# Danger_Shield-v17.net
KiCad netlist of a schematic drawn in EAGLE
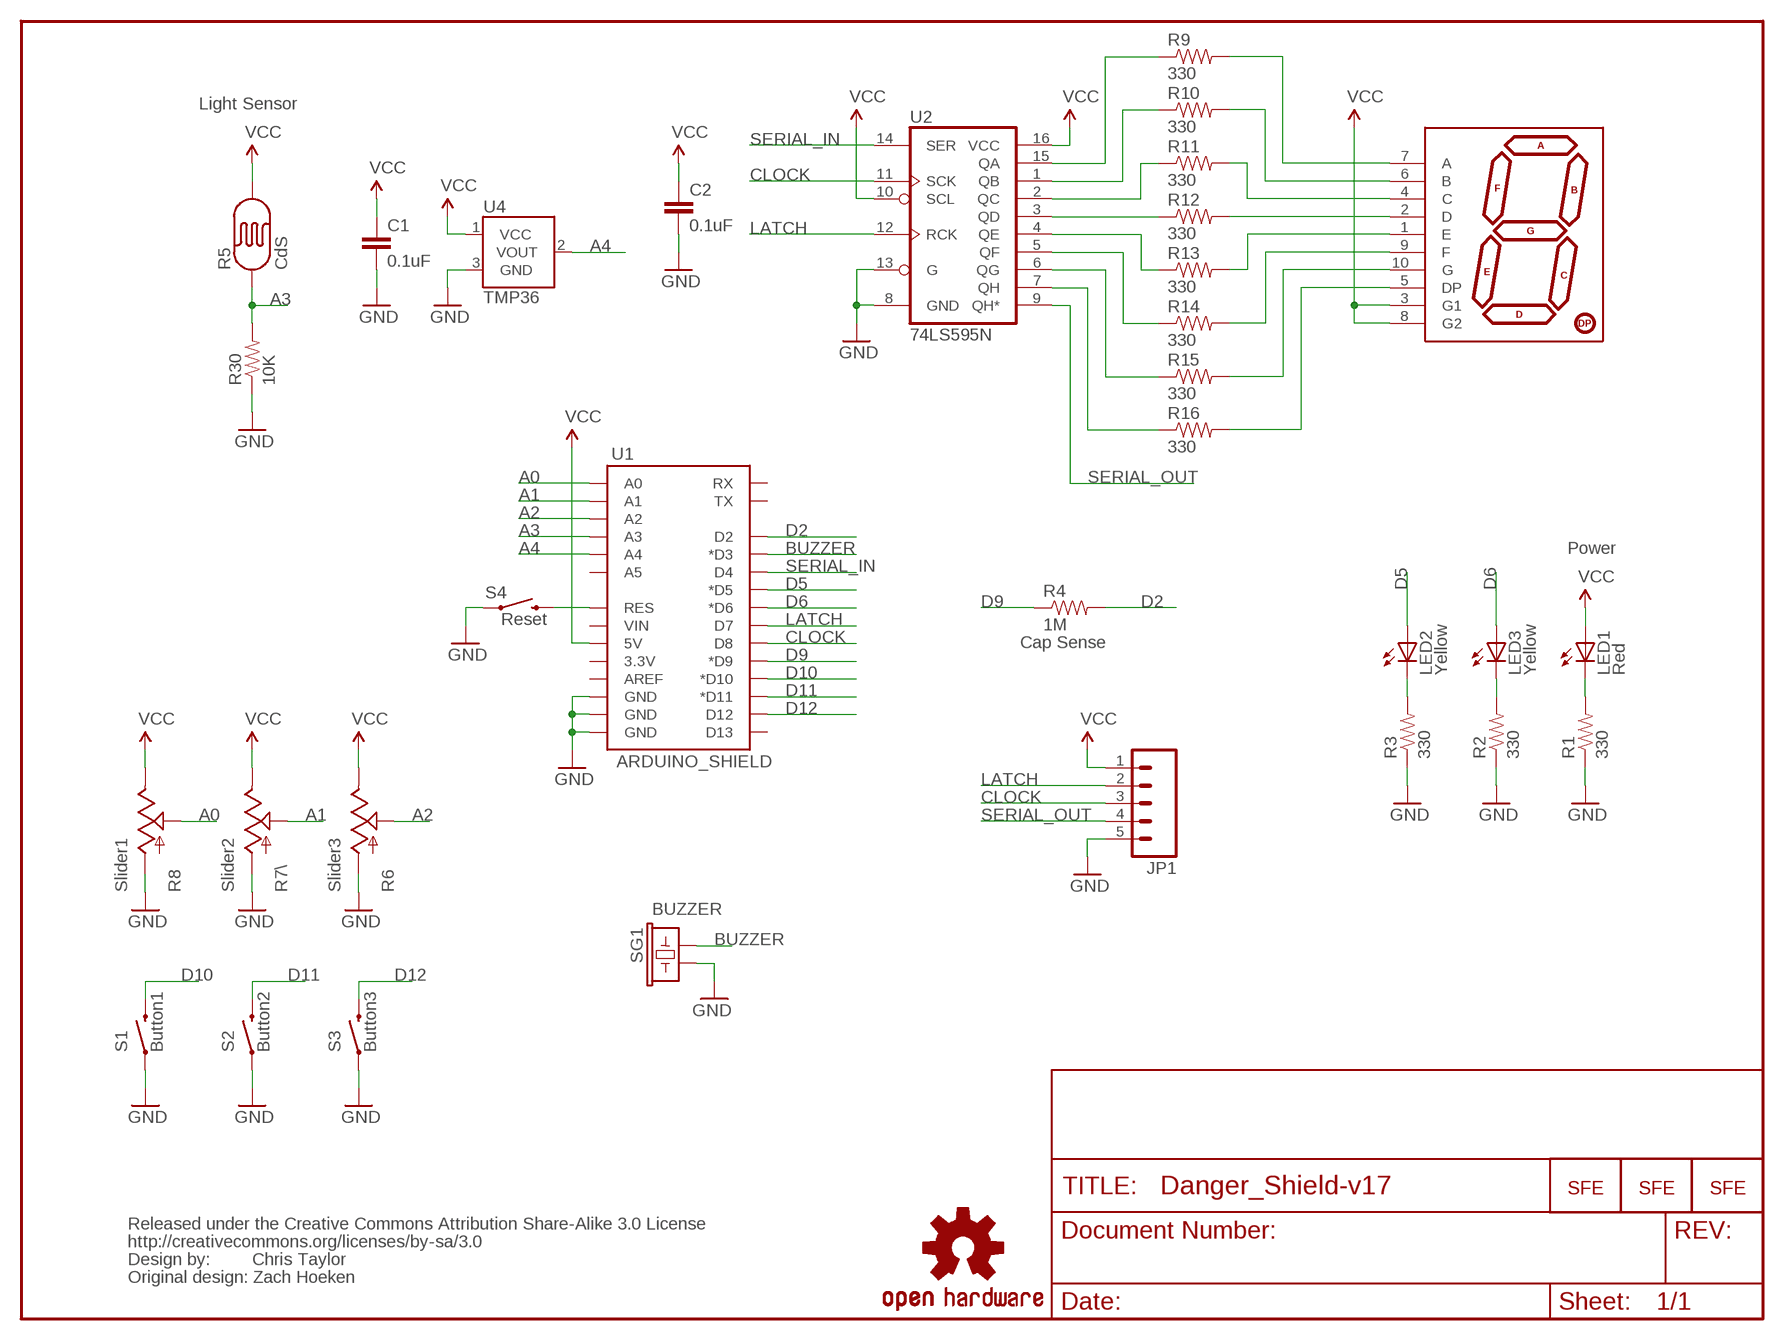
[diagram p0: schematic, sheet 1]

(export (version "E")
  (design (tool "Eeschema 10.0.6"))
  (components
    (comp (ref "C1")
      (value "0.1uF")
      (footprint "eagle-import:CAP-PTH-SMALL2")
      (libsource (lib "eagle-import") (part "CAPPTH2"))
    )
    (comp (ref "C2")
      (value "0.1uF")
      (footprint "eagle-import:CAP-PTH-SMALL2")
      (libsource (lib "eagle-import") (part "CAPPTH2"))
    )
    (comp (ref "JP1")
      (value "M05PTH")
      (footprint "eagle-import:1X05")
      (libsource (lib "eagle-import") (part "M05PTH"))
    )
    (comp (ref "JP2")
      (value "LOGO-SFENEW")
      (footprint "eagle-import:SFE-NEW-WEBLOGO")
      (libsource (lib "eagle-import") (part "LOGO-SFENEW"))
    )
    (comp (ref "JP3")
      (value "LOGO-SFENEW")
      (footprint "eagle-import:SFE-NEW-WEBLOGO")
      (libsource (lib "eagle-import") (part "LOGO-SFENEW"))
    )
    (comp (ref "JP5")
      (value "LOGO-SFESK")
      (footprint "eagle-import:SFE-LOGO-FLAME")
      (libsource (lib "eagle-import") (part "LOGO-SFESK"))
    )
    (comp (ref "LED1")
      (value "Red")
      (footprint "eagle-import:LED5MM")
      (libsource (lib "eagle-import") (part "LED5MM"))
    )
    (comp (ref "LED2")
      (value "Yellow")
      (footprint "eagle-import:LED5MM")
      (libsource (lib "eagle-import") (part "LED5MM"))
    )
    (comp (ref "LED3")
      (value "Yellow")
      (footprint "eagle-import:LED5MM")
      (libsource (lib "eagle-import") (part "LED5MM"))
    )
    (comp (ref "R1")
      (value "330")
      (footprint "eagle-import:AXIAL-0.3")
      (libsource (lib "eagle-import") (part "RESISTORAXIAL-0.3"))
    )
    (comp (ref "R2")
      (value "330")
      (footprint "eagle-import:AXIAL-0.3")
      (libsource (lib "eagle-import") (part "RESISTORAXIAL-0.3"))
    )
    (comp (ref "R3")
      (value "330")
      (footprint "eagle-import:AXIAL-0.3")
      (libsource (lib "eagle-import") (part "RESISTORAXIAL-0.3"))
    )
    (comp (ref "R4")
      (value "1M")
      (footprint "eagle-import:AXIAL-0.3")
      (libsource (lib "eagle-import") (part "RESISTORAXIAL-0.3"))
    )
    (comp (ref "R5")
      (value "CdS")
      (footprint "eagle-import:PHOTOCELL")
      (libsource (lib "eagle-import") (part "PHOTOCELLPTH"))
    )
    (comp (ref "R6")
      (value "Slider3")
      (footprint "eagle-import:SLIDER")
      (libsource (lib "eagle-import") (part "SLIDER"))
    )
    (comp (ref "R7\\")
      (value "Slider2")
      (footprint "eagle-import:SLIDER")
      (libsource (lib "eagle-import") (part "SLIDER"))
    )
    (comp (ref "R8")
      (value "Slider1")
      (footprint "eagle-import:SLIDER")
      (libsource (lib "eagle-import") (part "SLIDER"))
    )
    (comp (ref "R9")
      (value "330")
      (footprint "eagle-import:AXIAL-0.3")
      (libsource (lib "eagle-import") (part "RESISTORAXIAL-0.3"))
    )
    (comp (ref "R10")
      (value "330")
      (footprint "eagle-import:AXIAL-0.3")
      (libsource (lib "eagle-import") (part "RESISTORAXIAL-0.3"))
    )
    (comp (ref "R11")
      (value "330")
      (footprint "eagle-import:AXIAL-0.3")
      (libsource (lib "eagle-import") (part "RESISTORAXIAL-0.3"))
    )
    (comp (ref "R12")
      (value "330")
      (footprint "eagle-import:AXIAL-0.3")
      (libsource (lib "eagle-import") (part "RESISTORAXIAL-0.3"))
    )
    (comp (ref "R13")
      (value "330")
      (footprint "eagle-import:AXIAL-0.3")
      (libsource (lib "eagle-import") (part "RESISTORAXIAL-0.3"))
    )
    (comp (ref "R14")
      (value "330")
      (footprint "eagle-import:AXIAL-0.3")
      (libsource (lib "eagle-import") (part "RESISTORAXIAL-0.3"))
    )
    (comp (ref "R15")
      (value "330")
      (footprint "eagle-import:AXIAL-0.3")
      (libsource (lib "eagle-import") (part "RESISTORAXIAL-0.3"))
    )
    (comp (ref "R16")
      (value "330")
      (footprint "eagle-import:AXIAL-0.3")
      (libsource (lib "eagle-import") (part "RESISTORAXIAL-0.3"))
    )
    (comp (ref "R30")
      (value "10K")
      (footprint "eagle-import:AXIAL-0.3")
      (libsource (lib "eagle-import") (part "RESISTORAXIAL-0.3"))
    )
    (comp (ref "S1")
      (value "Button1")
      (footprint "eagle-import:TACTILE-PTH-12MM")
      (libsource (lib "eagle-import") (part "SWITCH-MOMENTARY-212MM"))
    )
    (comp (ref "S2")
      (value "Button2")
      (footprint "eagle-import:TACTILE-PTH-12MM")
      (libsource (lib "eagle-import") (part "SWITCH-MOMENTARY-212MM"))
    )
    (comp (ref "S3")
      (value "Button3")
      (footprint "eagle-import:TACTILE-PTH-12MM")
      (libsource (lib "eagle-import") (part "SWITCH-MOMENTARY-212MM"))
    )
    (comp (ref "S4")
      (value "Reset")
      (footprint "eagle-import:TACTILE-PTH")
      (libsource (lib "eagle-import") (part "SWITCH-MOMENTARY-2PTH"))
    )
    (comp (ref "SG1")
      (value "BUZZER")
      (footprint "eagle-import:BUZZER-12MM")
      (libsource (lib "eagle-import") (part "BUZZERPTH"))
    )
    (comp (ref "U$1")
      (value "CREATIVE_COMMONS")
      (footprint "eagle-import:CREATIVE_COMMONS")
      (libsource (lib "eagle-import") (part "CREATIVE_COMMONS"))
    )
    (comp (ref "U$2")
      (value "OSHW-LOGOM")
      (footprint "eagle-import:OSHW-LOGO-M")
      (libsource (lib "eagle-import") (part "OSHW-LOGOM"))
    )
    (comp (ref "U$6")
      (value "7-SEGMENT-DISPLAY-1\"-RED")
      (footprint "eagle-import:7-SEGMENT-1_PTH")
      (libsource (lib "eagle-import") (part "7-SEGMENT-DISPLAY-1{dblquote}-RED"))
    )
    (comp (ref "U1")
      (value "ARDUINO_SHIELD")
      (footprint "eagle-import:DUEMILANOVE_VIAS")
      (libsource (lib "eagle-import") (part "ARDUINO_SHIELDNO_SILK"))
    )
    (comp (ref "U2")
      (value "74LS595N")
      (footprint "eagle-import:DIL16")
      (libsource (lib "eagle-import") (part "74595NLS"))
    )
    (comp (ref "U4")
      (value "TMP36")
      (footprint "eagle-import:TO-92")
      (libsource (lib "eagle-import") (part "TMP36GT9"))
    )
  )
  (nets
    (net (code "1") (name "/A0") (class "Default")
      (node (ref "R8") (pin "2A") (pinfunction "S_2A") (pintype "passive"))
      (node (ref "U1") (pin "A0") (pinfunction "A0_A0") (pintype "bidirectional"))
    )
    (net (code "2") (name "/A1") (class "Default")
      (node (ref "R7\\") (pin "2A") (pinfunction "S_2A") (pintype "passive"))
      (node (ref "U1") (pin "A1") (pinfunction "A1_A1") (pintype "bidirectional"))
    )
    (net (code "3") (name "/A2") (class "Default")
      (node (ref "R6") (pin "2A") (pinfunction "S_2A") (pintype "passive"))
      (node (ref "U1") (pin "A2") (pinfunction "A2_A2") (pintype "bidirectional"))
    )
    (net (code "4") (name "/A3") (class "Default")
      (node (ref "R30") (pin "P$2") (pinfunction "2_P$2") (pintype "passive"))
      (node (ref "R5") (pin "1") (pinfunction "P$1_1") (pintype "bidirectional"))
      (node (ref "U1") (pin "A3") (pinfunction "A3_A3") (pintype "bidirectional"))
    )
    (net (code "5") (name "/A4") (class "Default")
      (node (ref "U1") (pin "A4") (pinfunction "A4_A4") (pintype "bidirectional"))
      (node (ref "U4") (pin "2") (pinfunction "VOUT_2") (pintype "bidirectional"))
    )
    (net (code "6") (name "/BUZZER") (class "Default")
      (node (ref "SG1") (pin "+") (pinfunction "1_+") (pintype "passive"))
      (node (ref "U1") (pin "D3") (pinfunction "*D3_D3") (pintype "bidirectional"))
    )
    (net (code "7") (name "/CLOCK") (class "Default")
      (node (ref "JP1") (pin "3") (pinfunction "3_3") (pintype "passive"))
      (node (ref "U1") (pin "D8") (pinfunction "D8_D8") (pintype "bidirectional"))
      (node (ref "U2") (pin "11") (pinfunction "SCK_11") (pintype "input"))
    )
    (net (code "8") (name "/D2") (class "Default")
      (node (ref "R4") (pin "P$2") (pinfunction "2_P$2") (pintype "passive"))
      (node (ref "U1") (pin "D2") (pinfunction "D2_D2") (pintype "bidirectional"))
    )
    (net (code "9") (name "/D5") (class "Default")
      (node (ref "LED2") (pin "A") (pinfunction "A_A") (pintype "passive"))
      (node (ref "U1") (pin "D5") (pinfunction "*D5_D5") (pintype "bidirectional"))
    )
    (net (code "10") (name "/D6") (class "Default")
      (node (ref "LED3") (pin "A") (pinfunction "A_A") (pintype "passive"))
      (node (ref "U1") (pin "D6") (pinfunction "*D6_D6") (pintype "bidirectional"))
    )
    (net (code "11") (name "/D9") (class "Default")
      (node (ref "R4") (pin "P$1") (pinfunction "1_P$1") (pintype "passive"))
      (node (ref "U1") (pin "D9") (pinfunction "*D9_D9") (pintype "bidirectional"))
    )
    (net (code "12") (name "/D10") (class "Default")
      (node (ref "S1") (pin "3") (pinfunction "2_3") (pintype "passive"))
      (node (ref "U1") (pin "D10") (pinfunction "*D10_D10") (pintype "bidirectional"))
    )
    (net (code "13") (name "/D11") (class "Default")
      (node (ref "S2") (pin "3") (pinfunction "2_3") (pintype "passive"))
      (node (ref "U1") (pin "D11") (pinfunction "*D11_D11") (pintype "bidirectional"))
    )
    (net (code "14") (name "/D12") (class "Default")
      (node (ref "S3") (pin "3") (pinfunction "2_3") (pintype "passive"))
      (node (ref "U1") (pin "D12") (pinfunction "D12_D12") (pintype "bidirectional"))
    )
    (net (code "15") (name "/LATCH") (class "Default")
      (node (ref "JP1") (pin "2") (pinfunction "2_2") (pintype "passive"))
      (node (ref "U1") (pin "D7") (pinfunction "D7_D7") (pintype "bidirectional"))
      (node (ref "U2") (pin "12") (pinfunction "RCK_12") (pintype "input"))
    )
    (net (code "16") (name "/SERIAL_IN") (class "Default")
      (node (ref "U1") (pin "D4") (pinfunction "D4_D4") (pintype "bidirectional"))
      (node (ref "U2") (pin "14") (pinfunction "SER_14") (pintype "input"))
    )
    (net (code "17") (name "/SERIAL_OUT") (class "Default")
      (node (ref "JP1") (pin "4") (pinfunction "4_4") (pintype "passive"))
      (node (ref "U2") (pin "9") (pinfunction "QH*_9") (pintype "tri_state"))
    )
    (net (code "18") (name "GND") (class "Default")
      (node (ref "C1") (pin "2") (pinfunction "2_2") (pintype "passive"))
      (node (ref "C2") (pin "2") (pinfunction "2_2") (pintype "passive"))
      (node (ref "JP1") (pin "5") (pinfunction "5_5") (pintype "passive"))
      (node (ref "R1") (pin "P$1") (pinfunction "1_P$1") (pintype "passive"))
      (node (ref "R2") (pin "P$1") (pinfunction "1_P$1") (pintype "passive"))
      (node (ref "R3") (pin "P$1") (pinfunction "1_P$1") (pintype "passive"))
      (node (ref "R30") (pin "P$1") (pinfunction "1_P$1") (pintype "passive"))
      (node (ref "R6") (pin "3") (pinfunction "A_3") (pintype "passive"))
      (node (ref "R7\\") (pin "3") (pinfunction "A_3") (pintype "passive"))
      (node (ref "R8") (pin "3") (pinfunction "A_3") (pintype "passive"))
      (node (ref "S1") (pin "1") (pinfunction "1_1") (pintype "passive"))
      (node (ref "S2") (pin "1") (pinfunction "1_1") (pintype "passive"))
      (node (ref "S3") (pin "1") (pinfunction "1_1") (pintype "passive"))
      (node (ref "S4") (pin "1") (pinfunction "1_1") (pintype "passive"))
      (node (ref "SG1") (pin "-") (pinfunction "2_-") (pintype "passive"))
      (node (ref "U1") (pin "GND@0") (pinfunction "GND_GND@0") (pintype "bidirectional"))
      (node (ref "U1") (pin "GND@1") (pinfunction "GND_GND@1") (pintype "bidirectional"))
      (node (ref "U1") (pin "GND@2") (pinfunction "GND_GND@2") (pintype "bidirectional"))
      (node (ref "U2") (pin "13") (pinfunction "G_13") (pintype "input"))
      (node (ref "U2") (pin "8") (pinfunction "GND_8") (pintype "power_in"))
      (node (ref "U4") (pin "3") (pinfunction "GND_3") (pintype "bidirectional"))
    )
    (net (code "19") (name "Net-(LED1-C)") (class "Default")
      (node (ref "LED1") (pin "K") (pinfunction "C_K") (pintype "passive"))
      (node (ref "R1") (pin "P$2") (pinfunction "2_P$2") (pintype "passive"))
    )
    (net (code "20") (name "Net-(LED2-C)") (class "Default")
      (node (ref "LED2") (pin "K") (pinfunction "C_K") (pintype "passive"))
      (node (ref "R3") (pin "P$2") (pinfunction "2_P$2") (pintype "passive"))
    )
    (net (code "21") (name "Net-(LED3-C)") (class "Default")
      (node (ref "LED3") (pin "K") (pinfunction "C_K") (pintype "passive"))
      (node (ref "R2") (pin "P$2") (pinfunction "2_P$2") (pintype "passive"))
    )
    (net (code "22") (name "Net-(R9-1)") (class "Default")
      (node (ref "R9") (pin "P$1") (pinfunction "1_P$1") (pintype "passive"))
      (node (ref "U2") (pin "15") (pinfunction "QA_15") (pintype "tri_state"))
    )
    (net (code "23") (name "Net-(R9-2)") (class "Default")
      (node (ref "R9") (pin "P$2") (pinfunction "2_P$2") (pintype "passive"))
      (node (ref "U$6") (pin "7") (pinfunction "A_7") (pintype "bidirectional"))
    )
    (net (code "24") (name "Net-(R10-1)") (class "Default")
      (node (ref "R10") (pin "P$1") (pinfunction "1_P$1") (pintype "passive"))
      (node (ref "U2") (pin "1") (pinfunction "QB_1") (pintype "tri_state"))
    )
    (net (code "25") (name "Net-(R10-2)") (class "Default")
      (node (ref "R10") (pin "P$2") (pinfunction "2_P$2") (pintype "passive"))
      (node (ref "U$6") (pin "6") (pinfunction "B_6") (pintype "bidirectional"))
    )
    (net (code "26") (name "Net-(R11-1)") (class "Default")
      (node (ref "R11") (pin "P$1") (pinfunction "1_P$1") (pintype "passive"))
      (node (ref "U2") (pin "2") (pinfunction "QC_2") (pintype "tri_state"))
    )
    (net (code "27") (name "Net-(R11-2)") (class "Default")
      (node (ref "R11") (pin "P$2") (pinfunction "2_P$2") (pintype "passive"))
      (node (ref "U$6") (pin "4") (pinfunction "C_4") (pintype "bidirectional"))
    )
    (net (code "28") (name "Net-(R12-1)") (class "Default")
      (node (ref "R12") (pin "P$1") (pinfunction "1_P$1") (pintype "passive"))
      (node (ref "U2") (pin "3") (pinfunction "QD_3") (pintype "tri_state"))
    )
    (net (code "29") (name "Net-(R12-2)") (class "Default")
      (node (ref "R12") (pin "P$2") (pinfunction "2_P$2") (pintype "passive"))
      (node (ref "U$6") (pin "2") (pinfunction "D_2") (pintype "bidirectional"))
    )
    (net (code "30") (name "Net-(R13-1)") (class "Default")
      (node (ref "R13") (pin "P$1") (pinfunction "1_P$1") (pintype "passive"))
      (node (ref "U2") (pin "4") (pinfunction "QE_4") (pintype "tri_state"))
    )
    (net (code "31") (name "Net-(R13-2)") (class "Default")
      (node (ref "R13") (pin "P$2") (pinfunction "2_P$2") (pintype "passive"))
      (node (ref "U$6") (pin "1") (pinfunction "E_1") (pintype "bidirectional"))
    )
    (net (code "32") (name "Net-(R14-1)") (class "Default")
      (node (ref "R14") (pin "P$1") (pinfunction "1_P$1") (pintype "passive"))
      (node (ref "U2") (pin "5") (pinfunction "QF_5") (pintype "tri_state"))
    )
    (net (code "33") (name "Net-(R14-2)") (class "Default")
      (node (ref "R14") (pin "P$2") (pinfunction "2_P$2") (pintype "passive"))
      (node (ref "U$6") (pin "9") (pinfunction "F_9") (pintype "bidirectional"))
    )
    (net (code "34") (name "Net-(R15-1)") (class "Default")
      (node (ref "R15") (pin "P$1") (pinfunction "1_P$1") (pintype "passive"))
      (node (ref "U2") (pin "6") (pinfunction "QG_6") (pintype "tri_state"))
    )
    (net (code "35") (name "Net-(R15-2)") (class "Default")
      (node (ref "R15") (pin "P$2") (pinfunction "2_P$2") (pintype "passive"))
      (node (ref "U$6") (pin "10") (pinfunction "G_10") (pintype "bidirectional"))
    )
    (net (code "36") (name "Net-(R16-1)") (class "Default")
      (node (ref "R16") (pin "P$1") (pinfunction "1_P$1") (pintype "passive"))
      (node (ref "U2") (pin "7") (pinfunction "QH_7") (pintype "tri_state"))
    )
    (net (code "37") (name "Net-(R16-2)") (class "Default")
      (node (ref "R16") (pin "P$2") (pinfunction "2_P$2") (pintype "passive"))
      (node (ref "U$6") (pin "5") (pinfunction "DP_5") (pintype "bidirectional"))
    )
    (net (code "38") (name "Net-(S4-2)") (class "Default")
      (node (ref "S4") (pin "3") (pinfunction "2_3") (pintype "passive"))
      (node (ref "U1") (pin "RES") (pinfunction "RES_RES") (pintype "bidirectional"))
    )
    (net (code "39") (name "VCC") (class "Default")
      (node (ref "C1") (pin "1") (pinfunction "1_1") (pintype "passive"))
      (node (ref "C2") (pin "1") (pinfunction "1_1") (pintype "passive"))
      (node (ref "JP1") (pin "1") (pinfunction "1_1") (pintype "passive"))
      (node (ref "LED1") (pin "A") (pinfunction "A_A") (pintype "passive"))
      (node (ref "R5") (pin "2") (pinfunction "P$2_2") (pintype "bidirectional"))
      (node (ref "R6") (pin "1") (pinfunction "E_1") (pintype "passive"))
      (node (ref "R7\\") (pin "1") (pinfunction "E_1") (pintype "passive"))
      (node (ref "R8") (pin "1") (pinfunction "E_1") (pintype "passive"))
      (node (ref "U$6") (pin "3") (pinfunction "G1_3") (pintype "bidirectional"))
      (node (ref "U$6") (pin "8") (pinfunction "G2_8") (pintype "bidirectional"))
      (node (ref "U1") (pin "5V") (pinfunction "5V_5V") (pintype "bidirectional"))
      (node (ref "U2") (pin "10") (pinfunction "SCL_10") (pintype "input"))
      (node (ref "U2") (pin "16") (pinfunction "VCC_16") (pintype "power_in"))
      (node (ref "U4") (pin "1") (pinfunction "VCC_1") (pintype "bidirectional"))
    )
    (net (code "40") (name "unconnected-(U1-Pad3.3V)") (class "Default")
      (node (ref "U1") (pin "3.3V") (pinfunction "3.3V_3.3V") (pintype "bidirectional"))
    )
    (net (code "41") (name "unconnected-(U1-PadA5)") (class "Default")
      (node (ref "U1") (pin "A5") (pinfunction "A5_A5") (pintype "bidirectional"))
    )
    (net (code "42") (name "unconnected-(U1-PadAREF)") (class "Default")
      (node (ref "U1") (pin "AREF") (pinfunction "AREF_AREF") (pintype "bidirectional"))
    )
    (net (code "43") (name "unconnected-(U1-PadD13)") (class "Default")
      (node (ref "U1") (pin "D13") (pinfunction "D13_D13") (pintype "bidirectional"))
    )
    (net (code "44") (name "unconnected-(U1-PadRX)") (class "Default")
      (node (ref "U1") (pin "RX") (pinfunction "RX_RX") (pintype "bidirectional"))
    )
    (net (code "45") (name "unconnected-(U1-PadTX)") (class "Default")
      (node (ref "U1") (pin "TX") (pinfunction "TX_TX") (pintype "bidirectional"))
    )
    (net (code "46") (name "unconnected-(U1-PadVIN)") (class "Default")
      (node (ref "U1") (pin "VIN") (pinfunction "VIN_VIN") (pintype "bidirectional"))
    )
  )
)
